# Sheet7.net
KiCad netlist of a schematic drawn in Altium Designer
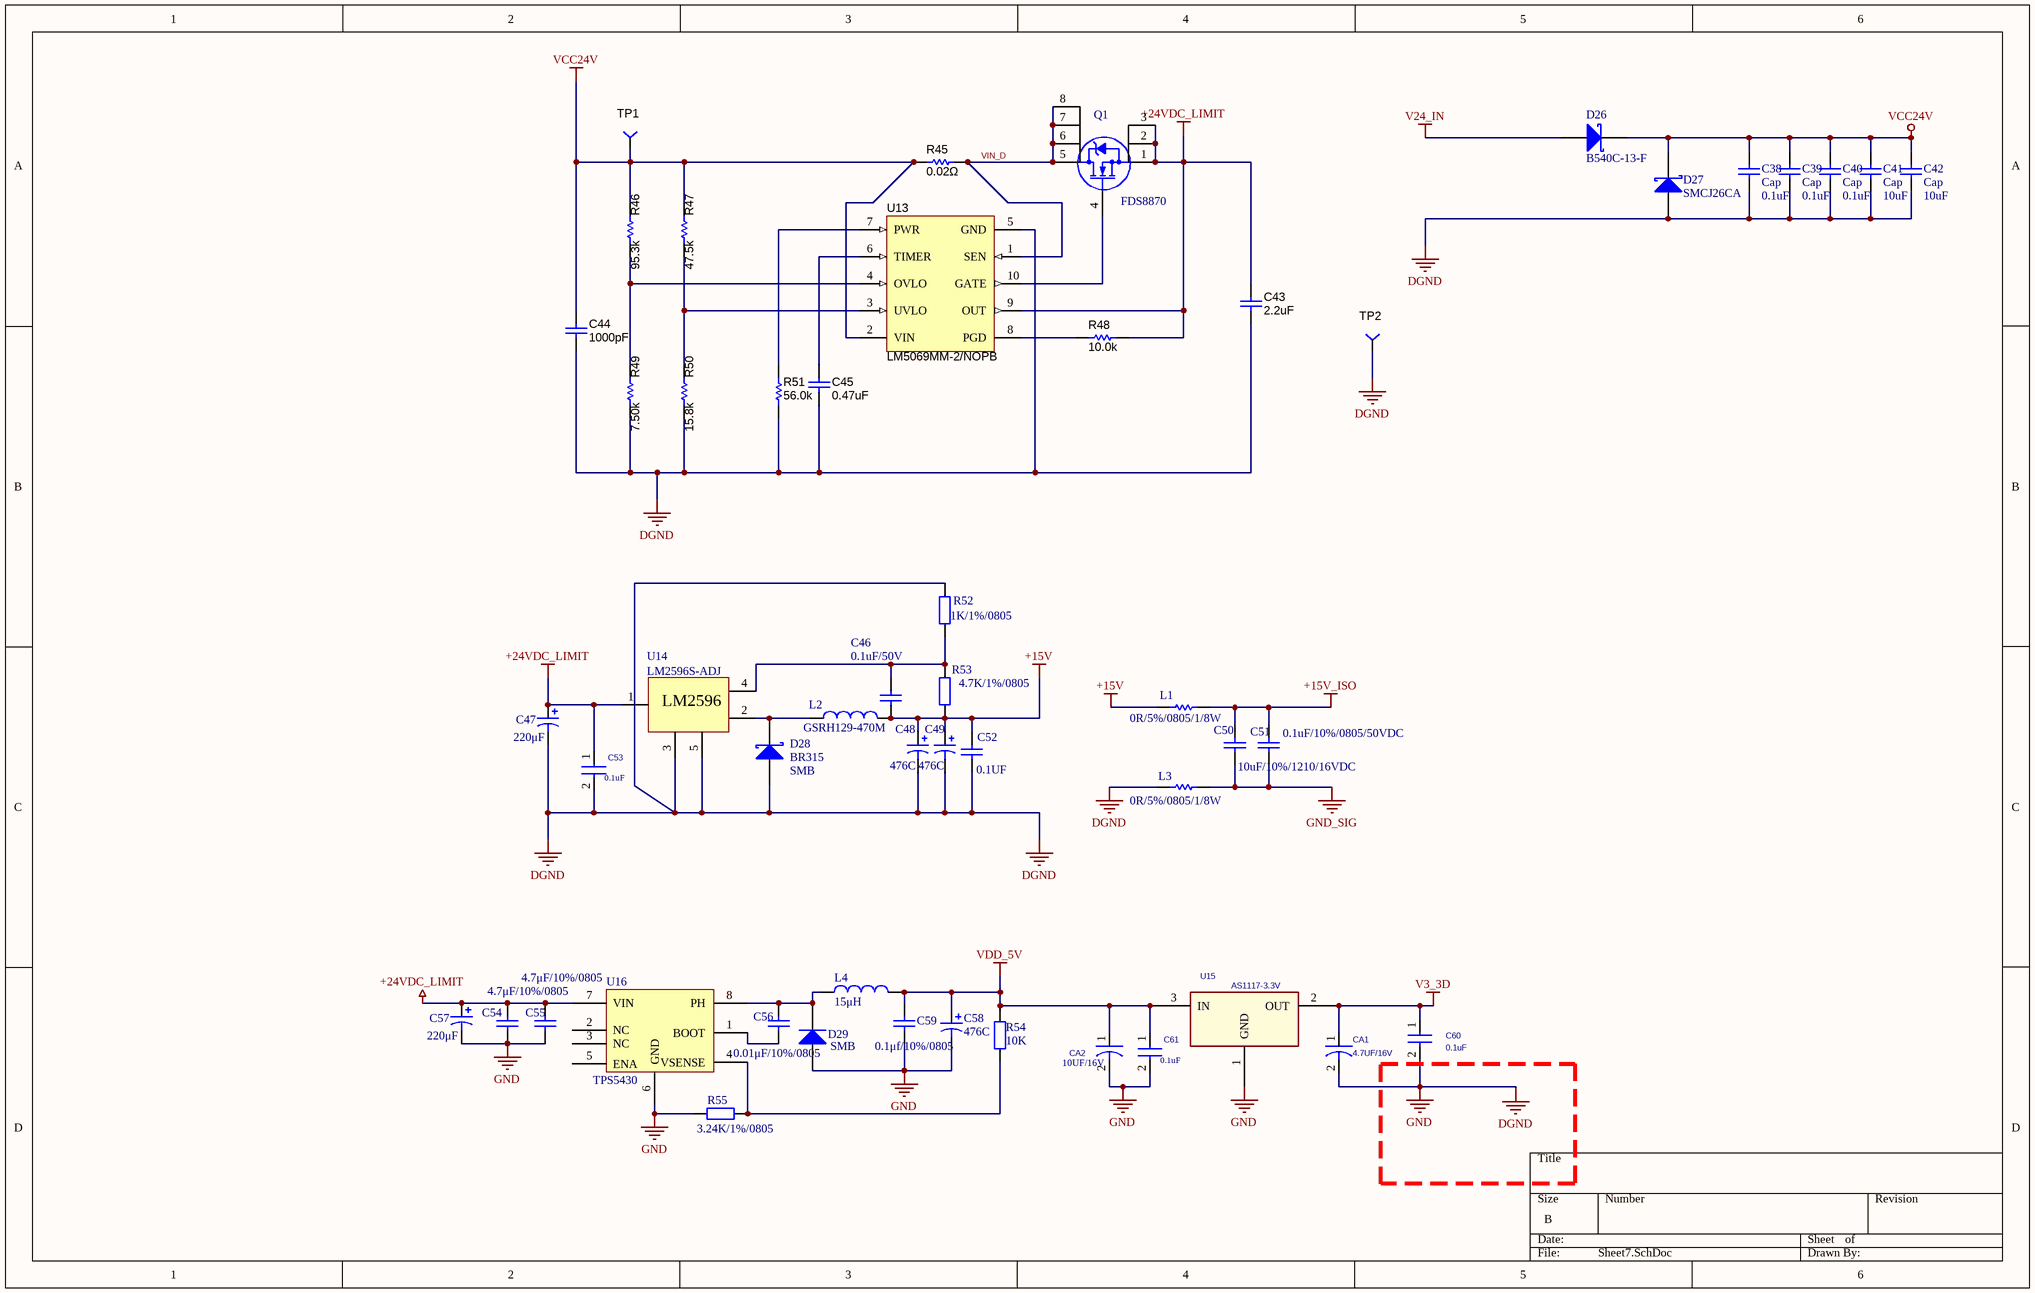
[diagram p0: Sheet7.SchDoc]

(export (version "E")
  (design (tool "Eeschema 10.0.6"))
  (components
    (comp (ref "C38")
      (value "Cap")
      (footprint "0805_cap")
      (description "Capacitor")
      (fields (field (name "ALTIUM_VALUE") "0.1uF") (field (name "PUBLISHER") "Altium Limited"))
      (libsource (lib "Miscellaneous Devices") (part "Cap"))
    )
    (comp (ref "C39")
      (value "Cap")
      (footprint "0805_cap")
      (description "Capacitor")
      (fields (field (name "ALTIUM_VALUE") "0.1uF") (field (name "PUBLISHER") "Altium Limited"))
      (libsource (lib "Miscellaneous Devices") (part "Cap"))
    )
    (comp (ref "C40")
      (value "Cap")
      (footprint "0805_cap")
      (description "Capacitor")
      (fields (field (name "ALTIUM_VALUE") "0.1uF") (field (name "PUBLISHER") "Altium Limited"))
      (libsource (lib "Miscellaneous Devices") (part "Cap"))
    )
    (comp (ref "C41")
      (value "Cap")
      (footprint "0805_cap")
      (description "Capacitor")
      (fields (field (name "ALTIUM_VALUE") "10uF") (field (name "PUBLISHER") "Altium Limited"))
      (libsource (lib "Miscellaneous Devices") (part "Cap"))
    )
    (comp (ref "C42")
      (value "Cap")
      (footprint "0805_cap")
      (description "Capacitor")
      (fields (field (name "ALTIUM_VALUE") "10uF") (field (name "PUBLISHER") "Altium Limited"))
      (libsource (lib "Miscellaneous Devices") (part "Cap"))
    )
    (comp (ref "C43")
      (value "GRM32ER72A225KA35L")
      (footprint "1210")
      (description "CAP, CERM, 2.2uF, 100V, +/-10%, X7R, 1210")
      (fields
        (field (name "VALUEDISPLAYED") "2.2uF")
        (field (name "MANUFACTURER") "MuRata")
        (field (name "PUBLISHER") "Texas Instruments")
      )
      (libsource (lib "Capacitor_Ceramic") (part "GRM32ER72A225KA35L"))
    )
    (comp (ref "C44")
      (value "06031C102JAT2A")
      (footprint "0805_cap")
      (description "CAP, CERM, 1000pF, 100V, +/-5%, X7R, 0603")
      (fields
        (field (name "VALUEDISPLAYED") "1000pF")
        (field (name "MANUFACTURER") "AVX")
        (field (name "PUBLISHER") "Texas Instruments")
      )
      (libsource (lib "Capacitor_Ceramic") (part "06031C102JAT2A"))
    )
    (comp (ref "C45")
      (value "UMK107ABJ474KA-T")
      (footprint "0805_cap")
      (description "CAP, CERM, 0.47uF, 50V, 10%, X5R, 0603")
      (fields
        (field (name "MANUFACTURER") "Taiyo Yuden")
        (field (name "VALUEDISPLAYED") "0.47uF")
        (field (name "PUBLISHER") "Texas Instruments")
      )
      (libsource (lib "TI-INDIA-ALTIUM") (part "UMK107ABJ474KA-T"))
    )
    (comp (ref "C46")
      (value "0.1uF/50V")
      (footprint "C-0805")
      (description "Capacitor")
      (libsource (lib "PCB_Project1_3") (part "Cap"))
    )
    (comp (ref "C47")
      (value "220μF")
      (footprint "CZ3.0/6.5")
      (description "Polarized Capacitor (Radial)")
      (fields (field (name "PUBLISHER") "Altium Limited"))
      (libsource (lib "Miscellaneous Devices") (part "Cap Pol1"))
    )
    (comp (ref "C48")
      (value "476C")
      (footprint "7343-43")
      (description "Polarized Capacitor (Radial)")
      (fields (field (name "PUBLISHER") "Altium Limited"))
      (libsource (lib "Miscellaneous Devices") (part "Cap Pol1"))
    )
    (comp (ref "C49")
      (value "476C")
      (footprint "7343-43")
      (description "Polarized Capacitor (Radial)")
      (fields (field (name "PUBLISHER") "Altium Limited"))
      (libsource (lib "Miscellaneous Devices") (part "Cap Pol1"))
    )
    (comp (ref "C50")
      (value "10uF/10%/1210/16VDC")
      (footprint "C-1210")
      (libsource (lib "浙江关西电机数据库") (part "CAP_Non-polarity"))
    )
    (comp (ref "C51")
      (value "0.1uF/10%/0805/50VDC")
      (footprint "C-0805")
      (libsource (lib "浙江关西电机数据库") (part "CAP_Non-polarity"))
    )
    (comp (ref "C52")
      (value "0.1UF")
      (footprint "C-0805")
      (description "Capacitor")
      (libsource (lib "PCB_Project1_3") (part "Cap"))
    )
    (comp (ref "C53") (value "0.1uF") (footprint "0805_CAP") (libsource (lib "v3") (part "C")))
    (comp (ref "C54")
      (value "4.7μF/10%/0805")
      (footprint "0805_CAP")
      (description "Capacitor")
      (fields (field (name "PUBLISHER") "Altium Limited"))
      (libsource (lib "Miscellaneous Devices") (part "Cap"))
    )
    (comp (ref "C55")
      (value "4.7μF/10%/0805")
      (footprint "0805_CAP")
      (description "Capacitor")
      (fields (field (name "PUBLISHER") "Altium Limited"))
      (libsource (lib "Miscellaneous Devices") (part "Cap"))
    )
    (comp (ref "C56")
      (value "0.01μF/10%/0805")
      (footprint "0805_CAP")
      (description "Capacitor")
      (fields (field (name "PUBLISHER") "Altium Limited"))
      (libsource (lib "Miscellaneous Devices") (part "Cap"))
    )
    (comp (ref "C57")
      (value "220μF")
      (footprint "CZ3.0/6.5")
      (description "Polarized Capacitor (Radial)")
      (fields (field (name "PUBLISHER") "Altium Limited"))
      (libsource (lib "Miscellaneous Devices") (part "Cap Pol1"))
    )
    (comp (ref "C58")
      (value "476C")
      (footprint "7343-43")
      (description "Polarized Capacitor (Radial)")
      (fields (field (name "PUBLISHER") "Altium Limited"))
      (libsource (lib "Miscellaneous Devices") (part "Cap Pol1"))
    )
    (comp (ref "C59")
      (value "0.1μf/10%/0805")
      (footprint "0805_CAP")
      (description "Capacitor")
      (fields (field (name "PUBLISHER") "Altium Limited"))
      (libsource (lib "Miscellaneous Devices") (part "Cap"))
    )
    (comp (ref "C60") (value "0.1uF") (footprint "0805_CAP") (libsource (lib "v3") (part "C")))
    (comp (ref "C61") (value "0.1uF") (footprint "0805_CAP") (libsource (lib "v3") (part "C")))
    (comp (ref "CA1") (value "4.7UF/16V") (footprint "3528cap") (libsource (lib "v3") (part "ECAP")))
    (comp (ref "CA2") (value "10UF/16V") (footprint "3528cap") (libsource (lib "v3") (part "ECAP")))
    (comp (ref "D26")
      (value "B540C-13-F")
      (footprint "SMB")
      (description "Schottky Diode")
      (fields (field (name "PUBLISHER") "Altium Limited"))
      (libsource (lib "Miscellaneous Devices") (part "D Schottky"))
    )
    (comp (ref "D27")
      (value "SMCJ26CA")
      (footprint "SMB")
      (description "Schottky Diode")
      (fields (field (name "PUBLISHER") "Altium Limited"))
      (libsource (lib "Miscellaneous Devices") (part "D Schottky"))
    )
    (comp (ref "D28")
      (value "D Schottky")
      (footprint "SMB")
      (fields (field (name "ALTIUM_UNNAMED_1") "BR315") (field (name "ALTIUM_UNNAMED_2") "SMB"))
      (libsource (lib "SCHLIBRARIES") (part "D Schottky"))
    )
    (comp (ref "D29")
      (value "SMB")
      (footprint "SMB")
      (description "3 Amp Medium Power Silicon Rectifier Diode")
      (fields (field (name "PUBLISHER") "Altium Limited"))
      (libsource (lib "Miscellaneous Devices") (part "Diode 1N5408"))
    )
    (comp (ref "L1")
      (value "0R/5%/0805/1/8W")
      (footprint "R-0805")
      (fields (field (name "PART NUMBER") "ASR-0010AA") (field (name "规格") "0R/5%/0805/1/8W"))
      (libsource (lib "浙江关西电机数据库") (part "RES_1"))
    )
    (comp (ref "L2")
      (value "GSRH129-470M")
      (footprint "GSDS104C2")
      (description "Inductor")
      (libsource (lib "Miscellaneous Devices") (part "Inductor"))
    )
    (comp (ref "L3")
      (value "0R/5%/0805/1/8W")
      (footprint "R-0805")
      (fields (field (name "PART NUMBER") "ASR-0010AA") (field (name "规格") "0R/5%/0805/1/8W"))
      (libsource (lib "浙江关西电机数据库") (part "RES_1"))
    )
    (comp (ref "L4")
      (value "15μH")
      (footprint "GSDS104C2")
      (description "Inductor")
      (fields (field (name "PUBLISHER") "Altium Limited"))
      (libsource (lib "Miscellaneous Devices") (part "Inductor"))
    )
    (comp (ref "Q1")
      (value "FDS8870")
      (footprint "SO-G8")
      (libsource (lib "SCHLIBRARIES") (part "MOSFET_N_8"))
    )
    (comp (ref "R45")
      (value "0.02Ω")
      (footprint "1206")
      (description "RES, 0.02 ohm, 1%, 1W, 1206")
      (fields
        (field (name "PARTNUMBER") "PRL1632-R020-F-T1")
        (field (name "MANUFACTURER") "Susumu Co Ltd")
        (field (name "PUBLISHER") "Texas Instruments")
      )
      (libsource (lib "Resistor_1206") (part "PRL1632-R020-F-T1"))
    )
    (comp (ref "R46")
      (value "95.3k")
      (footprint "0805")
      (description "RES, 95.3k ohm, 1%, 0.1W, 0603")
      (fields
        (field (name "PARTNUMBER") "CRCW060395K3FKEA")
        (field (name "MANUFACTURER") "Vishay-Dale")
        (field (name "PUBLISHER") "Texas Instruments")
      )
      (libsource (lib "Resistor_0603") (part "CRCW060395K3FKEA"))
    )
    (comp (ref "R47")
      (value "47.5k")
      (footprint "0805")
      (description "RES, 47.5k ohm, 1%, 0.1W, 0603")
      (fields
        (field (name "PARTNUMBER") "CRCW060347K5FKEA")
        (field (name "MANUFACTURER") "Vishay-Dale")
        (field (name "PUBLISHER") "Texas Instruments")
      )
      (libsource (lib "Resistor_0603") (part "CRCW060347K5FKEA"))
    )
    (comp (ref "R48")
      (value "10.0k")
      (footprint "0805")
      (description "RES, 10.0k ohm, 1%, 0.1W, 0603")
      (fields
        (field (name "PARTNUMBER") "CRCW060310K0FKEA")
        (field (name "MANUFACTURER") "Vishay-Dale")
        (field (name "PUBLISHER") "Texas Instruments")
      )
      (libsource (lib "Resistor_0603") (part "CRCW060310K0FKEA"))
    )
    (comp (ref "R49")
      (value "7.50k")
      (footprint "0805")
      (description "RES, 7.50k ohm, 1%, 0.1W, 0603")
      (fields
        (field (name "PARTNUMBER") "CRCW06037K50FKEA")
        (field (name "MANUFACTURER") "Vishay-Dale")
        (field (name "PUBLISHER") "Texas Instruments")
      )
      (libsource (lib "Resistor_0603") (part "CRCW06037K50FKEA"))
    )
    (comp (ref "R50")
      (value "15.8k")
      (footprint "0805")
      (description "RES, 15.8k ohm, 1%, 0.1W, 0603")
      (fields
        (field (name "PARTNUMBER") "CRCW060315K8FKEA")
        (field (name "MANUFACTURER") "Vishay-Dale")
        (field (name "PUBLISHER") "Texas Instruments")
      )
      (libsource (lib "Resistor_0603") (part "CRCW060315K8FKEA"))
    )
    (comp (ref "R51")
      (value "56.0k")
      (footprint "0805")
      (description "RES, 56.0k ohm, 0.1%, 0.1W, 0603")
      (fields
        (field (name "PARTNUMBER") "RG1608P-563-B-T5")
        (field (name "MANUFACTURER") "Susumu Co Ltd")
        (field (name "PUBLISHER") "Texas Instruments")
      )
      (libsource (lib "Resistor_0603") (part "RG1608P-563-B-T5"))
    )
    (comp (ref "R52")
      (value "1K/1%/0805")
      (footprint "0805")
      (description "Resistor")
      (fields (field (name "PUBLISHER") "Altium Limited"))
      (libsource (lib "Miscellaneous Devices") (part "Res2"))
    )
    (comp (ref "R53")
      (value "4.7K/1%/0805")
      (footprint "0805")
      (description "Resistor")
      (fields (field (name "PUBLISHER") "Altium Limited"))
      (libsource (lib "Miscellaneous Devices") (part "Res2"))
    )
    (comp (ref "R54")
      (value "10K")
      (footprint "0805")
      (description "Resistor")
      (fields (field (name "PUBLISHER") "Altium Limited"))
      (libsource (lib "Miscellaneous Devices") (part "Res2"))
    )
    (comp (ref "R55")
      (value "3.24K/1%/0805")
      (footprint "0805")
      (description "Resistor")
      (fields (field (name "PUBLISHER") "Altium Limited"))
      (libsource (lib "") (part "Res2_1"))
    )
    (comp (ref "TP1")
      (value "TP-040_RND")
      (footprint "TP-040_RND")
      (description "Test Point, O.040 Hole")
      (fields (field (name "MANUFACTURER") "Standard"))
      (libsource (lib "PADSlegacy_Hardware") (part "TP-040_RND"))
    )
    (comp (ref "TP2")
      (value "TP-040_RND")
      (footprint "TP-040_RND")
      (description "Test Point, O.040 Hole")
      (fields (field (name "MANUFACTURER") "Standard"))
      (libsource (lib "PADSlegacy_Hardware") (part "TP-040_RND"))
    )
    (comp (ref "U13")
      (value "LM5069MM-2/NOPB")
      (footprint "MUB10A_N")
      (fields
        (field (name "MANUFACTURER") "National Semiconductor")
        (field (name "PUBLISHER") "Altium Limited")
      )
      (libsource (lib "NSC MiscPower") (part "LM5069MM-2/NOPB"))
    )
    (comp (ref "U14")
      (value "LM2596S-ADJ")
      (footprint "TO-263(S)-5")
      (libsource (lib "PCB_Project1") (part "SWITCHING"))
    )
    (comp (ref "U15") (value "AS1117-3.3V") (libsource (lib "v3") (part "AS1117")))
    (comp (ref "U16") (value "TPS5430") (footprint "SO-G8") (libsource (lib "SCHLIBRARIES") (part "TPS5430")))
  )
  (nets
    (net (code "1") (name "+15V") (class "Default")
      (node (ref "C46") (pin "2") (pinfunction "2_2") (pintype "passive"))
      (node (ref "C48") (pin "1") (pinfunction "1_1") (pintype "passive"))
      (node (ref "C49") (pin "1") (pinfunction "1_1") (pintype "passive"))
      (node (ref "C52") (pin "2") (pinfunction "2_2") (pintype "passive"))
      (node (ref "L1") (pin "1") (pinfunction "1_1") (pintype "passive"))
      (node (ref "L2") (pin "2") (pinfunction "2_2") (pintype "passive"))
      (node (ref "R53") (pin "1") (pinfunction "1_1") (pintype "passive"))
    )
    (net (code "2") (name "+15V_ISO") (class "Default")
      (node (ref "C50") (pin "2") (pinfunction "2_2") (pintype "passive"))
      (node (ref "C51") (pin "2") (pinfunction "2_2") (pintype "passive"))
      (node (ref "L1") (pin "2") (pinfunction "2_2") (pintype "passive"))
    )
    (net (code "3") (name "+24VDC_LIMIT") (class "Default")
      (node (ref "C43") (pin "1") (pinfunction "1_1") (pintype "passive"))
      (node (ref "C47") (pin "1") (pinfunction "1_1") (pintype "passive"))
      (node (ref "C53") (pin "1") (pinfunction "1_1") (pintype "passive"))
      (node (ref "C54") (pin "2") (pinfunction "2_2") (pintype "passive"))
      (node (ref "C55") (pin "2") (pinfunction "2_2") (pintype "passive"))
      (node (ref "C57") (pin "1") (pinfunction "1_1") (pintype "passive"))
      (node (ref "Q1") (pin "1") (pinfunction "S_1") (pintype "passive"))
      (node (ref "Q1") (pin "2") (pinfunction "S_2") (pintype "passive"))
      (node (ref "Q1") (pin "3") (pinfunction "S_3") (pintype "passive"))
      (node (ref "R48") (pin "1") (pinfunction "1_1") (pintype "passive"))
      (node (ref "U13") (pin "9") (pinfunction "OUT_9") (pintype "output"))
      (node (ref "U14") (pin "1") (pinfunction "1_1") (pintype "passive"))
      (node (ref "U16") (pin "7") (pinfunction "VIN_7") (pintype "passive"))
    )
    (net (code "4") (name "/VIN_D") (class "Default")
      (node (ref "Q1") (pin "5") (pinfunction "D_5") (pintype "passive"))
      (node (ref "Q1") (pin "6") (pinfunction "D_6") (pintype "passive"))
      (node (ref "Q1") (pin "7") (pinfunction "D_7") (pintype "passive"))
      (node (ref "Q1") (pin "8") (pinfunction "D_8") (pintype "passive"))
      (node (ref "R45") (pin "2") (pinfunction "2_2") (pintype "passive"))
      (node (ref "U13") (pin "1") (pinfunction "SEN_1") (pintype "input"))
    )
    (net (code "5") (name "DGND") (class "Default")
      (node (ref "C38") (pin "1") (pinfunction "1_1") (pintype "passive"))
      (node (ref "C39") (pin "1") (pinfunction "1_1") (pintype "passive"))
      (node (ref "C40") (pin "1") (pinfunction "1_1") (pintype "passive"))
      (node (ref "C41") (pin "1") (pinfunction "1_1") (pintype "passive"))
      (node (ref "C42") (pin "1") (pinfunction "1_1") (pintype "passive"))
      (node (ref "C43") (pin "2") (pinfunction "2_2") (pintype "passive"))
      (node (ref "C44") (pin "2") (pinfunction "2_2") (pintype "passive"))
      (node (ref "C45") (pin "2") (pinfunction "2_2") (pintype "passive"))
      (node (ref "C47") (pin "2") (pinfunction "2_2") (pintype "passive"))
      (node (ref "C48") (pin "2") (pinfunction "2_2") (pintype "passive"))
      (node (ref "C49") (pin "2") (pinfunction "2_2") (pintype "passive"))
      (node (ref "C52") (pin "1") (pinfunction "1_1") (pintype "passive"))
      (node (ref "C53") (pin "2") (pinfunction "2_2") (pintype "passive"))
      (node (ref "C54") (pin "1") (pinfunction "1_1") (pintype "passive"))
      (node (ref "C55") (pin "1") (pinfunction "1_1") (pintype "passive"))
      (node (ref "C57") (pin "2") (pinfunction "2_2") (pintype "passive"))
      (node (ref "C58") (pin "2") (pinfunction "2_2") (pintype "passive"))
      (node (ref "C59") (pin "1") (pinfunction "1_1") (pintype "passive"))
      (node (ref "C60") (pin "2") (pinfunction "2_2") (pintype "passive"))
      (node (ref "C61") (pin "2") (pinfunction "2_2") (pintype "passive"))
      (node (ref "CA1") (pin "2") (pinfunction "2_2") (pintype "passive"))
      (node (ref "CA2") (pin "2") (pinfunction "2_2") (pintype "passive"))
      (node (ref "D27") (pin "1") (pinfunction "A_1") (pintype "passive"))
      (node (ref "D28") (pin "1") (pinfunction "A_1") (pintype "passive"))
      (node (ref "D29") (pin "1") (pinfunction "A_1") (pintype "passive"))
      (node (ref "L3") (pin "1") (pinfunction "1_1") (pintype "passive"))
      (node (ref "R49") (pin "1") (pinfunction "1_1") (pintype "passive"))
      (node (ref "R50") (pin "1") (pinfunction "1_1") (pintype "passive"))
      (node (ref "R51") (pin "1") (pinfunction "1_1") (pintype "passive"))
      (node (ref "R52") (pin "2") (pinfunction "2_2") (pintype "passive"))
      (node (ref "R55") (pin "2") (pinfunction "2_2") (pintype "passive"))
      (node (ref "TP2") (pin "1") (pinfunction "1_1") (pintype "passive"))
      (node (ref "U13") (pin "5") (pinfunction "GND_5") (pintype "power_in"))
      (node (ref "U14") (pin "3") (pinfunction "3_3") (pintype "passive"))
      (node (ref "U14") (pin "5") (pinfunction "5_5") (pintype "passive"))
      (node (ref "U15") (pin "1") (pinfunction "GND_1") (pintype "passive"))
      (node (ref "U16") (pin "6") (pinfunction "GND_6") (pintype "passive"))
    )
    (net (code "6") (name "GND_SIG") (class "Default")
      (node (ref "C50") (pin "1") (pinfunction "1_1") (pintype "passive"))
      (node (ref "C51") (pin "1") (pinfunction "1_1") (pintype "passive"))
      (node (ref "L3") (pin "2") (pinfunction "2_2") (pintype "passive"))
    )
    (net (code "7") (name "Net-(C46-Pad1)") (class "Default")
      (node (ref "C46") (pin "1") (pinfunction "1_1") (pintype "passive"))
      (node (ref "R52") (pin "1") (pinfunction "1_1") (pintype "passive"))
      (node (ref "R53") (pin "2") (pinfunction "2_2") (pintype "passive"))
      (node (ref "U14") (pin "4") (pinfunction "4_4") (pintype "passive"))
    )
    (net (code "8") (name "Net-(D28-K)") (class "Default")
      (node (ref "D28") (pin "2") (pinfunction "K_2") (pintype "passive"))
      (node (ref "L2") (pin "1") (pinfunction "1_1") (pintype "passive"))
      (node (ref "U14") (pin "2") (pinfunction "2_2") (pintype "passive"))
    )
    (net (code "9") (name "Net-(D29-K)") (class "Default")
      (node (ref "C56") (pin "2") (pinfunction "2_2") (pintype "passive"))
      (node (ref "D29") (pin "2") (pinfunction "K_2") (pintype "passive"))
      (node (ref "L4") (pin "1") (pinfunction "1_1") (pintype "passive"))
      (node (ref "U16") (pin "8") (pinfunction "PH_8") (pintype "passive"))
    )
    (net (code "10") (name "Net-(Q1-G)") (class "Default")
      (node (ref "Q1") (pin "4") (pinfunction "G_4") (pintype "passive"))
      (node (ref "U13") (pin "10") (pinfunction "GATE_10") (pintype "output"))
    )
    (net (code "11") (name "Net-(U13-OVLO)") (class "Default")
      (node (ref "R46") (pin "1") (pinfunction "1_1") (pintype "passive"))
      (node (ref "R49") (pin "2") (pinfunction "2_2") (pintype "passive"))
      (node (ref "U13") (pin "4") (pinfunction "OVLO_4") (pintype "input"))
    )
    (net (code "12") (name "Net-(U13-PGD)") (class "Default")
      (node (ref "R48") (pin "2") (pinfunction "2_2") (pintype "passive"))
      (node (ref "U13") (pin "8") (pinfunction "PGD_8") (pintype "open_collector"))
    )
    (net (code "13") (name "Net-(U13-PWR)") (class "Default")
      (node (ref "R51") (pin "2") (pinfunction "2_2") (pintype "passive"))
      (node (ref "U13") (pin "7") (pinfunction "PWR_7") (pintype "input"))
    )
    (net (code "14") (name "Net-(U13-TIMER)") (class "Default")
      (node (ref "C45") (pin "1") (pinfunction "1_1") (pintype "passive"))
      (node (ref "U13") (pin "6") (pinfunction "TIMER_6") (pintype "input"))
    )
    (net (code "15") (name "Net-(U13-UVLO)") (class "Default")
      (node (ref "R47") (pin "1") (pinfunction "1_1") (pintype "passive"))
      (node (ref "R50") (pin "2") (pinfunction "2_2") (pintype "passive"))
      (node (ref "U13") (pin "3") (pinfunction "UVLO_3") (pintype "input"))
    )
    (net (code "16") (name "Net-(U16-BOOT)") (class "Default")
      (node (ref "C56") (pin "1") (pinfunction "1_1") (pintype "passive"))
      (node (ref "U16") (pin "1") (pinfunction "BOOT_1") (pintype "passive"))
    )
    (net (code "17") (name "Net-(U16-VSENSE)") (class "Default")
      (node (ref "R54") (pin "1") (pinfunction "1_1") (pintype "passive"))
      (node (ref "R55") (pin "1") (pinfunction "1_1") (pintype "passive"))
      (node (ref "U16") (pin "4") (pinfunction "VSENSE_4") (pintype "passive"))
    )
    (net (code "18") (name "V3_3D") (class "Default")
      (node (ref "C60") (pin "1") (pinfunction "1_1") (pintype "passive"))
      (node (ref "CA1") (pin "1") (pinfunction "1_1") (pintype "passive"))
      (node (ref "U15") (pin "2") (pinfunction "OUT_2") (pintype "passive"))
    )
    (net (code "19") (name "V24_IN") (class "Default")
      (node (ref "D26") (pin "1") (pinfunction "A_1") (pintype "passive"))
    )
    (net (code "20") (name "VCC24V") (class "Default")
      (node (ref "C38") (pin "2") (pinfunction "2_2") (pintype "passive"))
      (node (ref "C39") (pin "2") (pinfunction "2_2") (pintype "passive"))
      (node (ref "C40") (pin "2") (pinfunction "2_2") (pintype "passive"))
      (node (ref "C41") (pin "2") (pinfunction "2_2") (pintype "passive"))
      (node (ref "C42") (pin "2") (pinfunction "2_2") (pintype "passive"))
      (node (ref "C44") (pin "1") (pinfunction "1_1") (pintype "passive"))
      (node (ref "D26") (pin "2") (pinfunction "K_2") (pintype "passive"))
      (node (ref "D27") (pin "2") (pinfunction "K_2") (pintype "passive"))
      (node (ref "R45") (pin "1") (pinfunction "1_1") (pintype "passive"))
      (node (ref "R46") (pin "2") (pinfunction "2_2") (pintype "passive"))
      (node (ref "R47") (pin "2") (pinfunction "2_2") (pintype "passive"))
      (node (ref "TP1") (pin "1") (pinfunction "1_1") (pintype "passive"))
      (node (ref "U13") (pin "2") (pinfunction "VIN_2") (pintype "power_in"))
    )
    (net (code "21") (name "VDD_5V") (class "Default")
      (node (ref "C58") (pin "1") (pinfunction "1_1") (pintype "passive"))
      (node (ref "C59") (pin "2") (pinfunction "2_2") (pintype "passive"))
      (node (ref "C61") (pin "1") (pinfunction "1_1") (pintype "passive"))
      (node (ref "CA2") (pin "1") (pinfunction "1_1") (pintype "passive"))
      (node (ref "L4") (pin "2") (pinfunction "2_2") (pintype "passive"))
      (node (ref "R54") (pin "2") (pinfunction "2_2") (pintype "passive"))
      (node (ref "U15") (pin "3") (pinfunction "IN_3") (pintype "passive"))
    )
    (net (code "22") (name "unconnected-(U16-ENA-Pad5)") (class "Default")
      (node (ref "U16") (pin "5") (pinfunction "ENA_5") (pintype "passive"))
    )
    (net (code "23") (name "unconnected-(U16-NC-Pad2)") (class "Default")
      (node (ref "U16") (pin "2") (pinfunction "NC_2") (pintype "passive"))
    )
    (net (code "24") (name "unconnected-(U16-NC-Pad3)") (class "Default")
      (node (ref "U16") (pin "3") (pinfunction "NC_3") (pintype "passive"))
    )
  )
)
